# question_5.net
KiCad netlist of a schematic drawn in EAGLE
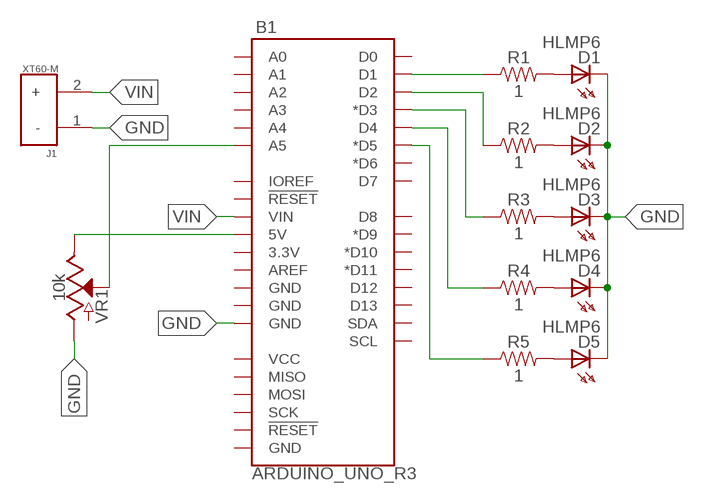
[diagram p0: schematic, sheet 1]

(export (version "E")
  (design (tool "Eeschema 10.0.6"))
  (components
    (comp (ref "B1")
      (value "ARDUINO_UNO_R3")
      (footprint "eagle-import:ARDUINO_R3")
      (libsource (lib "eagle-import") (part "ARDUINO_UNO_R3"))
    )
    (comp (ref "D1")
      (value "HLMP6")
      (footprint "eagle-import:HLMP6")
      (fields (field (name "MF") "AGILENT TECHNOLOGIES") (field (name "MPN") "HLMP-6500"))
      (libsource (lib "eagle-import") (part "HLMP6"))
    )
    (comp (ref "D2")
      (value "HLMP6")
      (footprint "eagle-import:HLMP6")
      (fields (field (name "MF") "AGILENT TECHNOLOGIES") (field (name "MPN") "HLMP-6500"))
      (libsource (lib "eagle-import") (part "HLMP6"))
    )
    (comp (ref "D3")
      (value "HLMP6")
      (footprint "eagle-import:HLMP6")
      (fields (field (name "MF") "AGILENT TECHNOLOGIES") (field (name "MPN") "HLMP-6500"))
      (libsource (lib "eagle-import") (part "HLMP6"))
    )
    (comp (ref "D4")
      (value "HLMP6")
      (footprint "eagle-import:HLMP6")
      (fields (field (name "MF") "AGILENT TECHNOLOGIES") (field (name "MPN") "HLMP-6500"))
      (libsource (lib "eagle-import") (part "HLMP6"))
    )
    (comp (ref "D5")
      (value "HLMP6")
      (footprint "eagle-import:HLMP6")
      (fields (field (name "MF") "AGILENT TECHNOLOGIES") (field (name "MPN") "HLMP-6500"))
      (libsource (lib "eagle-import") (part "HLMP6"))
    )
    (comp (ref "J1")
      (value "XT60-M")
      (footprint "eagle-import:AMASS_XT60-M")
      (fields (field (name "MF") "AMASS"))
      (libsource (lib "eagle-import") (part "XT60-M"))
    )
    (comp (ref "R1")
      (value "1")
      (footprint "eagle-import:0603")
      (libsource (lib "eagle-import") (part "1OHM-0603-1/10W-1%"))
    )
    (comp (ref "R2")
      (value "1")
      (footprint "eagle-import:0603")
      (libsource (lib "eagle-import") (part "1OHM-0603-1/10W-1%"))
    )
    (comp (ref "R3")
      (value "1")
      (footprint "eagle-import:0603")
      (libsource (lib "eagle-import") (part "1OHM-0603-1/10W-1%"))
    )
    (comp (ref "R4")
      (value "1")
      (footprint "eagle-import:0603")
      (libsource (lib "eagle-import") (part "1OHM-0603-1/10W-1%"))
    )
    (comp (ref "R5")
      (value "1")
      (footprint "eagle-import:0603")
      (libsource (lib "eagle-import") (part "1OHM-0603-1/10W-1%"))
    )
    (comp (ref "VR1")
      (value "10k")
      (footprint "eagle-import:SLIDER-SMALL")
      (libsource (lib "eagle-import") (part "POTENTIOMETER_SLIDE-20MM-1/10W-20%"))
    )
  )
  (nets
    (net (code "1") (name "GND") (class "Default")
      (node (ref "B1") (pin "GND@2") (pinfunction "GND_GND@2") (pintype "bidirectional"))
      (node (ref "D1") (pin "K") (pinfunction "K_K") (pintype "passive"))
      (node (ref "D2") (pin "K") (pinfunction "K_K") (pintype "passive"))
      (node (ref "D3") (pin "K") (pinfunction "K_K") (pintype "passive"))
      (node (ref "D4") (pin "K") (pinfunction "K_K") (pintype "passive"))
      (node (ref "D5") (pin "K") (pinfunction "K_K") (pintype "passive"))
      (node (ref "J1") (pin "1") (pinfunction "-_1") (pintype "passive"))
      (node (ref "VR1") (pin "BOTTOM") (pinfunction "A_BOTTOM") (pintype "passive"))
    )
    (net (code "2") (name "Net-(B1-*D3)") (class "Default")
      (node (ref "B1") (pin "D3") (pinfunction "*D3_D3") (pintype "bidirectional"))
      (node (ref "R3") (pin "1") (pinfunction "1_1") (pintype "passive"))
    )
    (net (code "3") (name "Net-(B1-*D5)") (class "Default")
      (node (ref "B1") (pin "D5") (pinfunction "*D5_D5") (pintype "bidirectional"))
      (node (ref "R5") (pin "1") (pinfunction "1_1") (pintype "passive"))
    )
    (net (code "4") (name "Net-(B1-PadD1)") (class "Default")
      (node (ref "B1") (pin "D1") (pinfunction "D1_D1") (pintype "bidirectional"))
      (node (ref "R1") (pin "1") (pinfunction "1_1") (pintype "passive"))
    )
    (net (code "5") (name "Net-(B1-PadD2)") (class "Default")
      (node (ref "B1") (pin "D2") (pinfunction "D2_D2") (pintype "bidirectional"))
      (node (ref "R2") (pin "1") (pinfunction "1_1") (pintype "passive"))
    )
    (net (code "6") (name "Net-(B1-PadD4)") (class "Default")
      (node (ref "B1") (pin "D4") (pinfunction "D4_D4") (pintype "bidirectional"))
      (node (ref "R4") (pin "1") (pinfunction "1_1") (pintype "passive"))
    )
    (net (code "7") (name "Net-(D1-PadA)") (class "Default")
      (node (ref "D1") (pin "A") (pinfunction "A_A") (pintype "passive"))
      (node (ref "R1") (pin "2") (pinfunction "2_2") (pintype "passive"))
    )
    (net (code "8") (name "Net-(D2-PadA)") (class "Default")
      (node (ref "D2") (pin "A") (pinfunction "A_A") (pintype "passive"))
      (node (ref "R2") (pin "2") (pinfunction "2_2") (pintype "passive"))
    )
    (net (code "9") (name "Net-(D3-PadA)") (class "Default")
      (node (ref "D3") (pin "A") (pinfunction "A_A") (pintype "passive"))
      (node (ref "R3") (pin "2") (pinfunction "2_2") (pintype "passive"))
    )
    (net (code "10") (name "Net-(D4-PadA)") (class "Default")
      (node (ref "D4") (pin "A") (pinfunction "A_A") (pintype "passive"))
      (node (ref "R4") (pin "2") (pinfunction "2_2") (pintype "passive"))
    )
    (net (code "11") (name "Net-(D5-PadA)") (class "Default")
      (node (ref "D5") (pin "A") (pinfunction "A_A") (pintype "passive"))
      (node (ref "R5") (pin "2") (pinfunction "2_2") (pintype "passive"))
    )
    (net (code "12") (name "Net-(VR1-E)") (class "Default")
      (node (ref "B1") (pin "5V") (pinfunction "5V_5V") (pintype "bidirectional"))
      (node (ref "VR1") (pin "TOP") (pinfunction "E_TOP") (pintype "passive"))
    )
    (net (code "13") (name "Net-(VR1-S)") (class "Default")
      (node (ref "B1") (pin "A5") (pinfunction "A5_A5") (pintype "bidirectional"))
      (node (ref "VR1") (pin "WIPER") (pinfunction "S_WIPER") (pintype "passive"))
    )
    (net (code "14") (name "VIN") (class "Default")
      (node (ref "B1") (pin "VIN") (pinfunction "VIN_VIN") (pintype "bidirectional"))
      (node (ref "J1") (pin "2") (pinfunction "+_2") (pintype "passive"))
    )
    (net (code "15") (name "unconnected-(B1-*D6-PadD6)") (class "Default")
      (node (ref "B1") (pin "D6") (pinfunction "*D6_D6") (pintype "bidirectional"))
    )
    (net (code "16") (name "unconnected-(B1-*D9-PadD9)") (class "Default")
      (node (ref "B1") (pin "D9") (pinfunction "*D9_D9") (pintype "bidirectional"))
    )
    (net (code "17") (name "unconnected-(B1-*D10-PadD10)") (class "Default")
      (node (ref "B1") (pin "D10") (pinfunction "*D10_D10") (pintype "bidirectional"))
    )
    (net (code "18") (name "unconnected-(B1-*D11-PadD11)") (class "Default")
      (node (ref "B1") (pin "D11") (pinfunction "*D11_D11") (pintype "bidirectional"))
    )
    (net (code "19") (name "unconnected-(B1-GND-PadGND@1)") (class "Default")
      (node (ref "B1") (pin "GND@1") (pinfunction "GND_GND@1") (pintype "bidirectional"))
    )
    (net (code "20") (name "unconnected-(B1-GND-PadGND@3)") (class "Default")
      (node (ref "B1") (pin "GND@3") (pinfunction "GND_GND@3") (pintype "bidirectional"))
    )
    (net (code "21") (name "unconnected-(B1-GND-PadGND@4)") (class "Default")
      (node (ref "B1") (pin "GND@4") (pinfunction "GND_GND@4") (pintype "bidirectional"))
    )
    (net (code "22") (name "unconnected-(B1-Pad3.3V)") (class "Default")
      (node (ref "B1") (pin "3.3V") (pinfunction "3.3V_3.3V") (pintype "bidirectional"))
    )
    (net (code "23") (name "unconnected-(B1-PadA0)") (class "Default")
      (node (ref "B1") (pin "A0") (pinfunction "A0_A0") (pintype "bidirectional"))
    )
    (net (code "24") (name "unconnected-(B1-PadA1)") (class "Default")
      (node (ref "B1") (pin "A1") (pinfunction "A1_A1") (pintype "bidirectional"))
    )
    (net (code "25") (name "unconnected-(B1-PadA2)") (class "Default")
      (node (ref "B1") (pin "A2") (pinfunction "A2_A2") (pintype "bidirectional"))
    )
    (net (code "26") (name "unconnected-(B1-PadA3)") (class "Default")
      (node (ref "B1") (pin "A3") (pinfunction "A3_A3") (pintype "bidirectional"))
    )
    (net (code "27") (name "unconnected-(B1-PadA4)") (class "Default")
      (node (ref "B1") (pin "A4") (pinfunction "A4_A4") (pintype "bidirectional"))
    )
    (net (code "28") (name "unconnected-(B1-PadAREF)") (class "Default")
      (node (ref "B1") (pin "AREF") (pinfunction "AREF_AREF") (pintype "bidirectional"))
    )
    (net (code "29") (name "unconnected-(B1-PadD0)") (class "Default")
      (node (ref "B1") (pin "D0") (pinfunction "D0_D0") (pintype "bidirectional"))
    )
    (net (code "30") (name "unconnected-(B1-PadD7)") (class "Default")
      (node (ref "B1") (pin "D7") (pinfunction "D7_D7") (pintype "bidirectional"))
    )
    (net (code "31") (name "unconnected-(B1-PadD8)") (class "Default")
      (node (ref "B1") (pin "D8") (pinfunction "D8_D8") (pintype "bidirectional"))
    )
    (net (code "32") (name "unconnected-(B1-PadD12)") (class "Default")
      (node (ref "B1") (pin "D12") (pinfunction "D12_D12") (pintype "bidirectional"))
    )
    (net (code "33") (name "unconnected-(B1-PadD13)") (class "Default")
      (node (ref "B1") (pin "D13") (pinfunction "D13_D13") (pintype "bidirectional"))
    )
    (net (code "34") (name "unconnected-(B1-PadIOREF)") (class "Default")
      (node (ref "B1") (pin "IOREF") (pinfunction "IOREF_IOREF") (pintype "bidirectional"))
    )
    (net (code "35") (name "unconnected-(B1-PadMISO)") (class "Default")
      (node (ref "B1") (pin "MISO") (pinfunction "MISO_MISO") (pintype "bidirectional"))
    )
    (net (code "36") (name "unconnected-(B1-PadMOSI)") (class "Default")
      (node (ref "B1") (pin "MOSI") (pinfunction "MOSI_MOSI") (pintype "bidirectional"))
    )
    (net (code "37") (name "unconnected-(B1-PadSCK)") (class "Default")
      (node (ref "B1") (pin "SCK") (pinfunction "SCK_SCK") (pintype "bidirectional"))
    )
    (net (code "38") (name "unconnected-(B1-PadSCL)") (class "Default")
      (node (ref "B1") (pin "SCL") (pinfunction "SCL_SCL") (pintype "bidirectional"))
    )
    (net (code "39") (name "unconnected-(B1-PadSDA)") (class "Default")
      (node (ref "B1") (pin "SDA") (pinfunction "SDA_SDA") (pintype "bidirectional"))
    )
    (net (code "40") (name "unconnected-(B1-PadVCC)") (class "Default")
      (node (ref "B1") (pin "VCC") (pinfunction "VCC_VCC") (pintype "bidirectional"))
    )
    (net (code "41") (name "unconnected-(B1-~{RESET}-PadRESET@1)") (class "Default")
      (node (ref "B1") (pin "RESET@1") (pinfunction "~{RESET}_RESET@1") (pintype "bidirectional"))
    )
    (net (code "42") (name "unconnected-(B1-~{RESET}-PadRESET@2)") (class "Default")
      (node (ref "B1") (pin "RESET@2") (pinfunction "~{RESET}_RESET@2") (pintype "bidirectional"))
    )
  )
)
